# Skematic.net
KiCad netlist of a schematic drawn in EAGLE
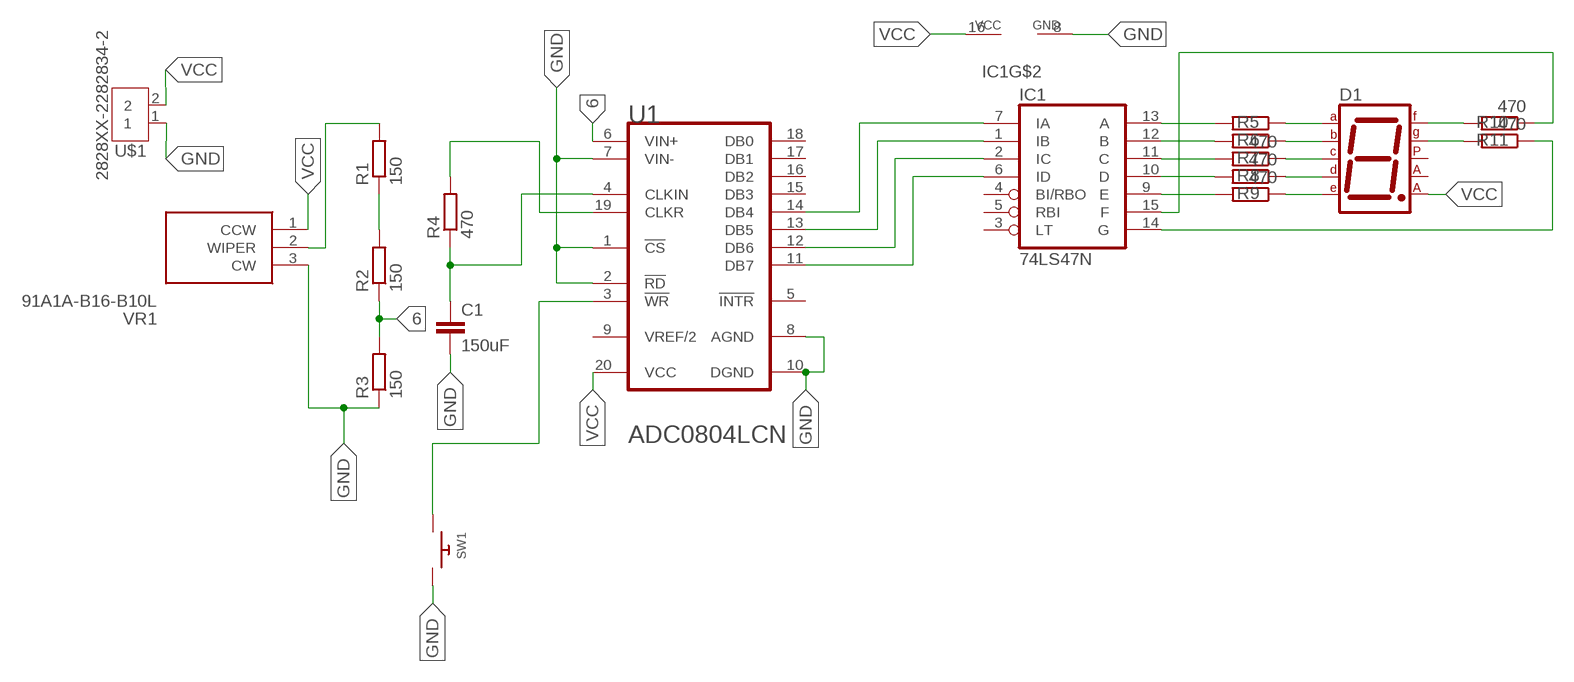
[diagram p0: schematic, sheet 1]

(export (version "E")
  (design (tool "Eeschema 10.0.6"))
  (components
    (comp (ref "C1")
      (value "150uF")
      (footprint "eagle-import:C025-025X050")
      (libsource (lib "eagle-import") (part "C-EU025-025X050"))
    )
    (comp (ref "D1")
      (value "7SEG-CA")
      (footprint "eagle-import:7SEG-13")
      (libsource (lib "eagle-import") (part "7SEG-CA"))
    )
    (comp (ref "IC1")
      (value "74LS47N")
      (footprint "eagle-import:DIL16")
      (libsource (lib "eagle-import") (part "7447NLS"))
    )
    (comp (ref "R1")
      (value "150")
      (footprint "eagle-import:0207_10")
      (libsource (lib "eagle-import") (part "R-EU_0207/10"))
    )
    (comp (ref "R2")
      (value "150")
      (footprint "eagle-import:0207_10")
      (libsource (lib "eagle-import") (part "R-EU_0207/10"))
    )
    (comp (ref "R3")
      (value "150")
      (footprint "eagle-import:0207_10")
      (libsource (lib "eagle-import") (part "R-EU_0207/10"))
    )
    (comp (ref "R4")
      (value "470")
      (footprint "eagle-import:0207_10")
      (libsource (lib "eagle-import") (part "R-EU_0207/10"))
    )
    (comp (ref "R5")
      (value "470")
      (footprint "eagle-import:0207_10")
      (libsource (lib "eagle-import") (part "R-EU_0207/10"))
    )
    (comp (ref "R6")
      (value "470")
      (footprint "eagle-import:0207_10")
      (libsource (lib "eagle-import") (part "R-EU_0207/10"))
    )
    (comp (ref "R7")
      (value "470")
      (footprint "eagle-import:0207_10")
      (libsource (lib "eagle-import") (part "R-EU_0207/10"))
    )
    (comp (ref "R8")
      (value "470")
      (footprint "eagle-import:0207_10")
      (libsource (lib "eagle-import") (part "R-EU_0207/10"))
    )
    (comp (ref "R9")
      (value "470")
      (footprint "eagle-import:0207_10")
      (libsource (lib "eagle-import") (part "R-EU_0207/10"))
    )
    (comp (ref "R10")
      (value "470")
      (footprint "eagle-import:0207_10")
      (libsource (lib "eagle-import") (part "R-EU_0207/10"))
    )
    (comp (ref "R11")
      (value "470")
      (footprint "eagle-import:0207_10")
      (libsource (lib "eagle-import") (part "R-EU_0207/10"))
    )
    (comp (ref "SW1")
      (value "SWITCH_PUSHBUTTONEVQ-PE")
      (footprint "eagle-import:TACT_PANA-EVQ")
      (libsource (lib "eagle-import") (part "SWITCH_PUSHBUTTONEVQ-PE"))
    )
    (comp (ref "U$1")
      (value "2828XX-2282834-2")
      (footprint "eagle-import:TERMBLK_254-2N")
      (libsource (lib "eagle-import") (part "2828XX-2282834-2"))
    )
    (comp (ref "U1")
      (value "TI_NATIONAL_SEMICONDUCTOR_ADC0804LCNTI_NATIONAL_SEMICONDUCTOR_ADC0804LCN_0_0")
      (footprint "eagle-import:TI_NATIONAL_SEMICONDUCTOR_ADC0804LCN_0")
      (fields (field (name "MF") "TI National Semiconductor") (field (name "MPN") "ADC0804LCN"))
      (libsource (lib "eagle-import") (part "TI_NATIONAL_SEMICONDUCTOR_ADC0804LCNTI_NATIONAL_SEMICONDUCTOR_ADC0804LCN_0_0"))
    )
    (comp (ref "VR1")
      (value "91A1A-B16-B10L")
      (footprint "eagle-import:91A1AB16B10L")
      (fields (field (name "MOUSER_PART_NUMBER") "652-91A1A-B16-B10L"))
      (libsource (lib "eagle-import") (part "91A1A-B16-B10L"))
    )
  )
  (nets
    (net (code "1") (name "/VREF{slash}2") (class "Default")
      (node (ref "U1") (pin "9") (pinfunction "VREF/2_9") (pintype "power_in"))
    )
    (net (code "2") (name "6") (class "Default")
      (node (ref "R2") (pin "1") (pinfunction "1_1") (pintype "passive"))
      (node (ref "R3") (pin "2") (pinfunction "2_2") (pintype "passive"))
      (node (ref "U1") (pin "6") (pinfunction "VIN+_6") (pintype "input"))
    )
    (net (code "3") (name "GND") (class "Default")
      (node (ref "C1") (pin "2") (pinfunction "2_2") (pintype "passive"))
      (node (ref "IC1") (pin "8") (pinfunction "GND_8") (pintype "power_in"))
      (node (ref "R3") (pin "1") (pinfunction "1_1") (pintype "passive"))
      (node (ref "SW1") (pin "P$2") (pinfunction "P$2_P$2") (pintype "passive"))
      (node (ref "U$1") (pin "1") (pinfunction "1_1") (pintype "bidirectional"))
      (node (ref "U1") (pin "1") (pinfunction "~{CS}_1") (pintype "input"))
      (node (ref "U1") (pin "10") (pinfunction "DGND_10") (pintype "power_in"))
      (node (ref "U1") (pin "2") (pinfunction "~{RD}_2") (pintype "input"))
      (node (ref "U1") (pin "7") (pinfunction "VIN-_7") (pintype "input"))
      (node (ref "U1") (pin "8") (pinfunction "AGND_8") (pintype "power_in"))
      (node (ref "VR1") (pin "3") (pinfunction "CW_3") (pintype "bidirectional"))
    )
    (net (code "4") (name "Net-(D1-A)") (class "Default")
      (node (ref "D1") (pin "7") (pinfunction "A_7") (pintype "passive"))
      (node (ref "R5") (pin "1") (pinfunction "1_1") (pintype "passive"))
    )
    (net (code "5") (name "Net-(D1-B)") (class "Default")
      (node (ref "D1") (pin "6") (pinfunction "B_6") (pintype "passive"))
      (node (ref "R6") (pin "1") (pinfunction "1_1") (pintype "passive"))
    )
    (net (code "6") (name "Net-(D1-C)") (class "Default")
      (node (ref "D1") (pin "4") (pinfunction "C_4") (pintype "passive"))
      (node (ref "R7") (pin "1") (pinfunction "1_1") (pintype "passive"))
    )
    (net (code "7") (name "Net-(D1-D)") (class "Default")
      (node (ref "D1") (pin "2") (pinfunction "D_2") (pintype "passive"))
      (node (ref "R8") (pin "1") (pinfunction "1_1") (pintype "passive"))
    )
    (net (code "8") (name "Net-(D1-E)") (class "Default")
      (node (ref "D1") (pin "1") (pinfunction "E_1") (pintype "passive"))
      (node (ref "R9") (pin "1") (pinfunction "1_1") (pintype "passive"))
    )
    (net (code "9") (name "Net-(D1-F)") (class "Default")
      (node (ref "D1") (pin "9") (pinfunction "F_9") (pintype "passive"))
      (node (ref "R10") (pin "2") (pinfunction "2_2") (pintype "passive"))
    )
    (net (code "10") (name "Net-(D1-G)") (class "Default")
      (node (ref "D1") (pin "10") (pinfunction "G_10") (pintype "passive"))
      (node (ref "R11") (pin "2") (pinfunction "2_2") (pintype "passive"))
    )
    (net (code "11") (name "Net-(IC1A-A)") (class "Default")
      (node (ref "IC1") (pin "13") (pinfunction "A_13") (pintype "output"))
      (node (ref "R5") (pin "2") (pinfunction "2_2") (pintype "passive"))
    )
    (net (code "12") (name "Net-(IC1A-B)") (class "Default")
      (node (ref "IC1") (pin "12") (pinfunction "B_12") (pintype "output"))
      (node (ref "R6") (pin "2") (pinfunction "2_2") (pintype "passive"))
    )
    (net (code "13") (name "Net-(IC1A-C)") (class "Default")
      (node (ref "IC1") (pin "11") (pinfunction "C_11") (pintype "output"))
      (node (ref "R7") (pin "2") (pinfunction "2_2") (pintype "passive"))
    )
    (net (code "14") (name "Net-(IC1A-D)") (class "Default")
      (node (ref "IC1") (pin "10") (pinfunction "D_10") (pintype "output"))
      (node (ref "R8") (pin "2") (pinfunction "2_2") (pintype "passive"))
    )
    (net (code "15") (name "Net-(IC1A-E)") (class "Default")
      (node (ref "IC1") (pin "9") (pinfunction "E_9") (pintype "output"))
      (node (ref "R9") (pin "2") (pinfunction "2_2") (pintype "passive"))
    )
    (net (code "16") (name "Net-(IC1A-F)") (class "Default")
      (node (ref "IC1") (pin "15") (pinfunction "F_15") (pintype "output"))
      (node (ref "R10") (pin "1") (pinfunction "1_1") (pintype "passive"))
    )
    (net (code "17") (name "Net-(IC1A-G)") (class "Default")
      (node (ref "IC1") (pin "14") (pinfunction "G_14") (pintype "output"))
      (node (ref "R11") (pin "1") (pinfunction "1_1") (pintype "passive"))
    )
    (net (code "18") (name "Net-(IC1A-IA)") (class "Default")
      (node (ref "IC1") (pin "7") (pinfunction "IA_7") (pintype "input"))
      (node (ref "U1") (pin "14") (pinfunction "DB4_14") (pintype "output"))
    )
    (net (code "19") (name "Net-(IC1A-IB)") (class "Default")
      (node (ref "IC1") (pin "1") (pinfunction "IB_1") (pintype "input"))
      (node (ref "U1") (pin "13") (pinfunction "DB5_13") (pintype "output"))
    )
    (net (code "20") (name "Net-(IC1A-IC)") (class "Default")
      (node (ref "IC1") (pin "2") (pinfunction "IC_2") (pintype "input"))
      (node (ref "U1") (pin "12") (pinfunction "DB6_12") (pintype "output"))
    )
    (net (code "21") (name "Net-(IC1A-ID)") (class "Default")
      (node (ref "IC1") (pin "6") (pinfunction "ID_6") (pintype "input"))
      (node (ref "U1") (pin "11") (pinfunction "DB7_11") (pintype "output"))
    )
    (net (code "22") (name "Net-(R1-Pad1)") (class "Default")
      (node (ref "R1") (pin "1") (pinfunction "1_1") (pintype "passive"))
      (node (ref "R2") (pin "2") (pinfunction "2_2") (pintype "passive"))
    )
    (net (code "23") (name "Net-(U1-CLKIN)") (class "Default")
      (node (ref "C1") (pin "1") (pinfunction "1_1") (pintype "passive"))
      (node (ref "R4") (pin "1") (pinfunction "1_1") (pintype "passive"))
      (node (ref "U1") (pin "4") (pinfunction "CLKIN_4") (pintype "input"))
    )
    (net (code "24") (name "Net-(U1-CLKR)") (class "Default")
      (node (ref "R4") (pin "2") (pinfunction "2_2") (pintype "passive"))
      (node (ref "U1") (pin "19") (pinfunction "CLKR_19") (pintype "input"))
    )
    (net (code "25") (name "Net-(U1-~{WR})") (class "Default")
      (node (ref "SW1") (pin "P$1") (pinfunction "P$1_P$1") (pintype "passive"))
      (node (ref "U1") (pin "3") (pinfunction "~{WR}_3") (pintype "input"))
    )
    (net (code "26") (name "Net-(VR1-WIPER)") (class "Default")
      (node (ref "R1") (pin "2") (pinfunction "2_2") (pintype "passive"))
      (node (ref "VR1") (pin "2") (pinfunction "WIPER_2") (pintype "bidirectional"))
    )
    (net (code "27") (name "VCC") (class "Default")
      (node (ref "D1") (pin "8") (pinfunction "CA2_8") (pintype "passive"))
      (node (ref "IC1") (pin "16") (pinfunction "VCC_16") (pintype "power_in"))
      (node (ref "U$1") (pin "2") (pinfunction "2_2") (pintype "bidirectional"))
      (node (ref "U1") (pin "20") (pinfunction "VCC_20") (pintype "power_in"))
      (node (ref "VR1") (pin "1") (pinfunction "CCW_1") (pintype "bidirectional"))
    )
    (net (code "28") (name "unconnected-(D1-CA1-Pad3)") (class "Default")
      (node (ref "D1") (pin "3") (pinfunction "CA1_3") (pintype "passive"))
    )
    (net (code "29") (name "unconnected-(D1-DP-Pad5)") (class "Default")
      (node (ref "D1") (pin "5") (pinfunction "DP_5") (pintype "passive"))
    )
    (net (code "30") (name "unconnected-(IC1A-BI{slash}RBO-Pad4)") (class "Default")
      (node (ref "IC1") (pin "4") (pinfunction "BI/RBO_4") (pintype "input"))
    )
    (net (code "31") (name "unconnected-(IC1A-LT-Pad3)") (class "Default")
      (node (ref "IC1") (pin "3") (pinfunction "LT_3") (pintype "input"))
    )
    (net (code "32") (name "unconnected-(IC1A-RBI-Pad5)") (class "Default")
      (node (ref "IC1") (pin "5") (pinfunction "RBI_5") (pintype "input"))
    )
    (net (code "33") (name "unconnected-(U1-DB0-Pad18)") (class "Default")
      (node (ref "U1") (pin "18") (pinfunction "DB0_18") (pintype "output"))
    )
    (net (code "34") (name "unconnected-(U1-DB1-Pad17)") (class "Default")
      (node (ref "U1") (pin "17") (pinfunction "DB1_17") (pintype "output"))
    )
    (net (code "35") (name "unconnected-(U1-DB2-Pad16)") (class "Default")
      (node (ref "U1") (pin "16") (pinfunction "DB2_16") (pintype "output"))
    )
    (net (code "36") (name "unconnected-(U1-DB3-Pad15)") (class "Default")
      (node (ref "U1") (pin "15") (pinfunction "DB3_15") (pintype "output"))
    )
    (net (code "37") (name "unconnected-(U1-~{INTR}-Pad5)") (class "Default")
      (node (ref "U1") (pin "5") (pinfunction "~{INTR}_5") (pintype "output"))
    )
  )
)
